# Spindle_Control.net
KiCad netlist of a schematic drawn in Altium Designer
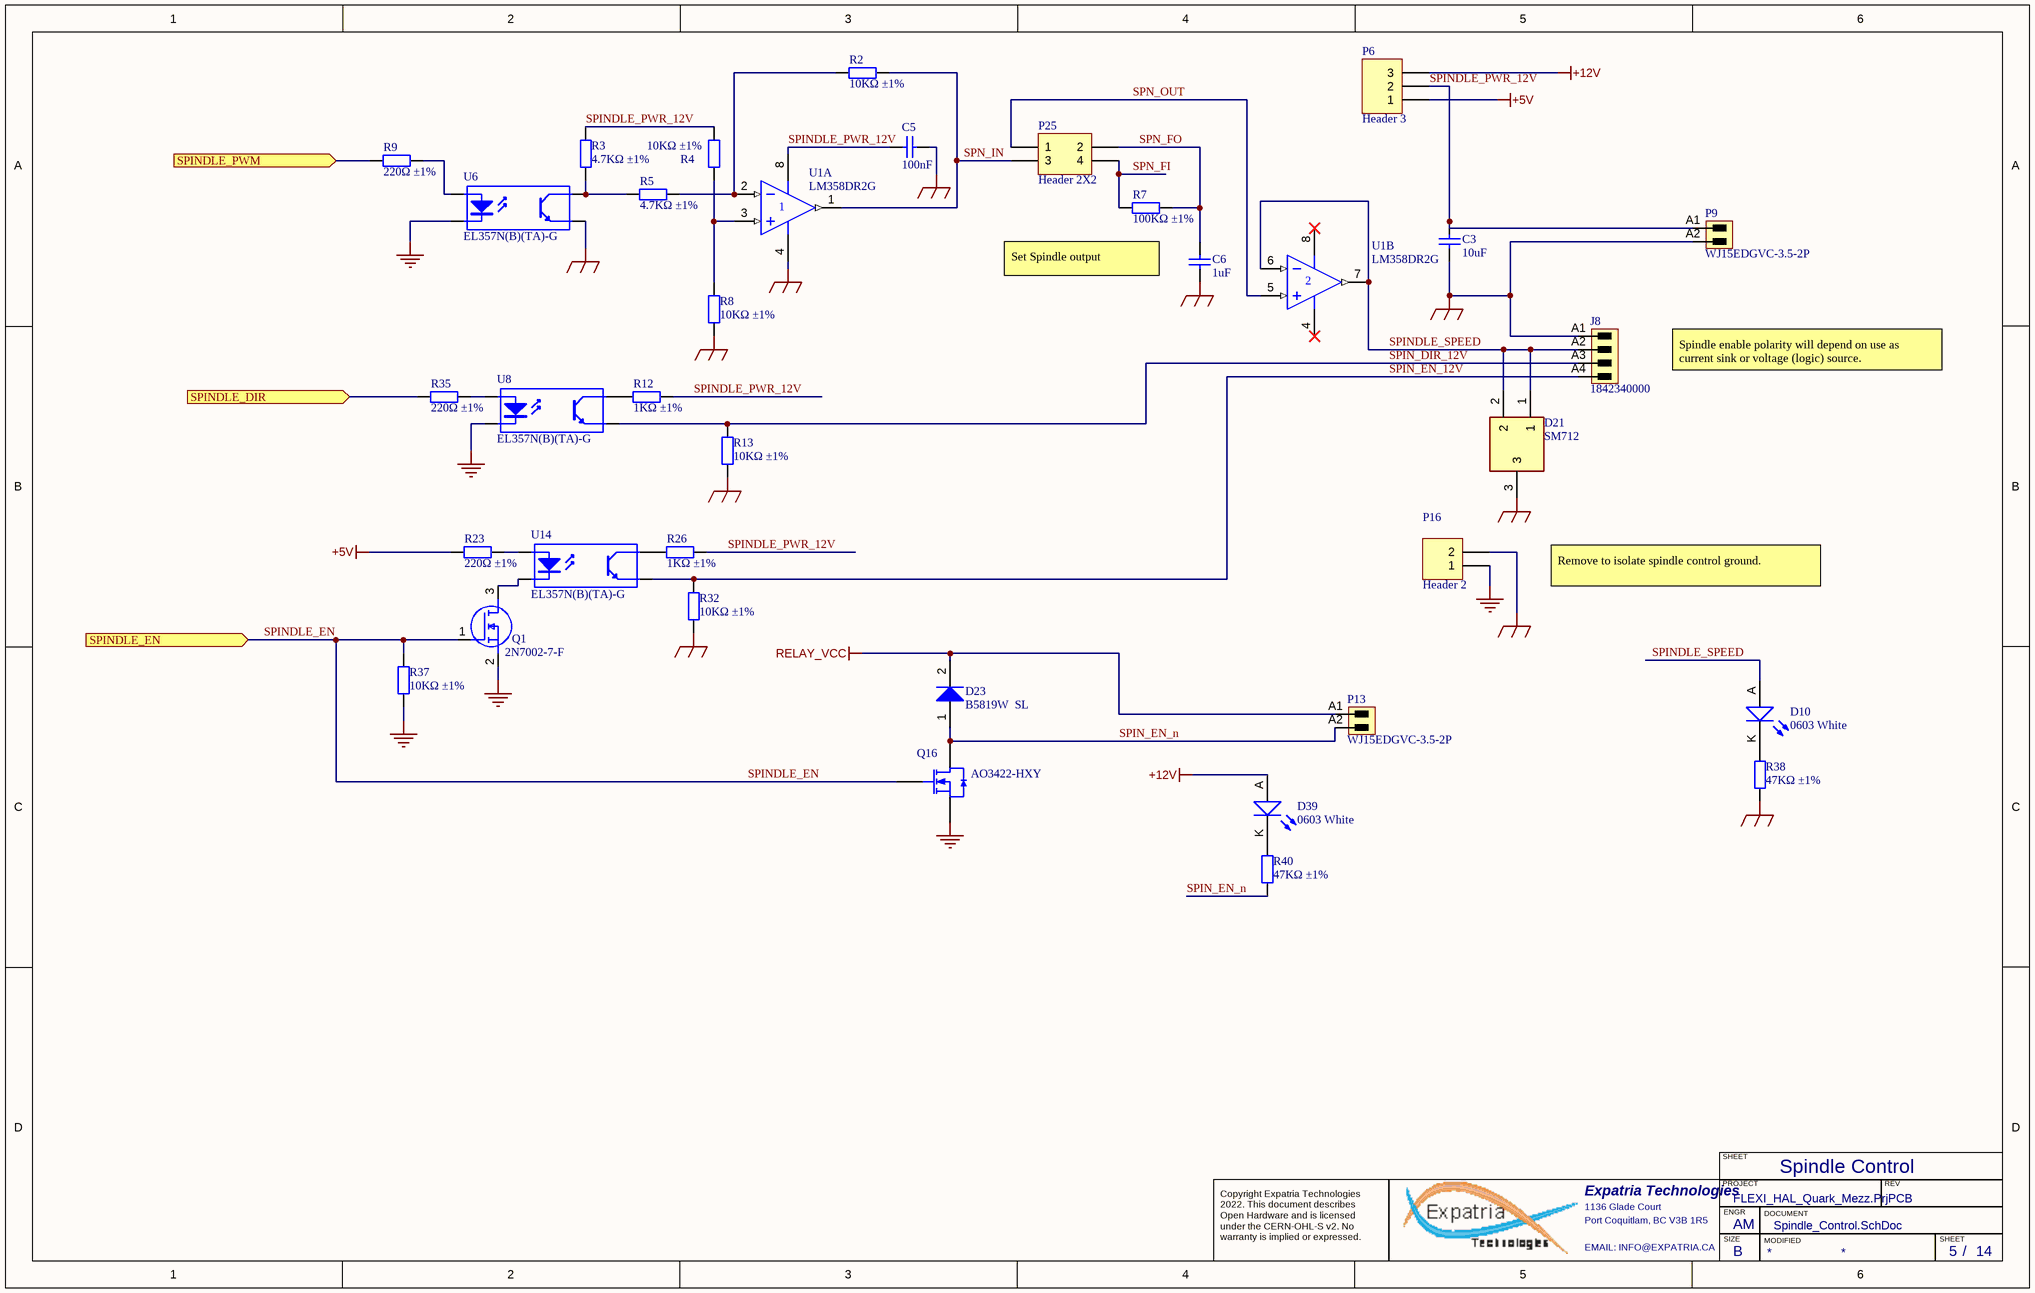
[diagram p0: Spindle_Control.SchDoc]

(export (version "E")
  (design (tool "Eeschema 10.0.6"))
  (components
    (comp (ref "C3")
      (value "10uF")
      (footprint "1206_C")
      (description "Chip capacitors")
      (fields
        (field (name "MANUFACTURER") "Samsung Electro-Mechanics")
        (field (name "PARTNUMBER") "CL31A106KBHNNNE")
      )
      (libsource (lib "Cap") (part "1206 10uF (106) 10% 50V"))
    )
    (comp (ref "C5")
      (value "100nF")
      (footprint "0603_C")
      (description "Chip capacitors")
      (fields (field (name "MANUFACTURER") "YAGEO") (field (name "PARTNUMBER") "CC0603KRX7R9BB104"))
      (libsource (lib "Cap") (part "0603 100nF (104) 10% 50V"))
    )
    (comp (ref "C6")
      (value "1uF")
      (footprint "0603_C")
      (description "Chip capacitors")
      (fields
        (field (name "MANUFACTURER") "Samsung Electro-Mechanics")
        (field (name "PARTNUMBER") "CL10A105KB8NNNC")
      )
      (libsource (lib "Cap") (part "0603 1uF (105) 10% 50V"))
    )
    (comp (ref "D10")
      (value "0603 White")
      (footprint "0603_LED_S1")
      (description "LED")
      (libsource (lib "LED") (part "0603 LED White"))
    )
    (comp (ref "D21")
      (value "SM712")
      (footprint "SamacSys:SOT95P230X117-3N")
      (description "Bidirectional 12V (Max), 7V (Max) 7.5V / 13.3V 10V / 20V 12A(8/20us) SOT-23-3 TVS RoHS")
      (libsource (lib "*") (part "CDSOT23-SM712"))
    )
    (comp (ref "D23")
      (value "B5819W  SL")
      (footprint "SOD-123")
      (description "Schottky Diode")
      (libsource (lib "Diode") (part "SOD-123 B5819W  SL"))
    )
    (comp (ref "D39")
      (value "0603 White")
      (footprint "0603_LED_S1")
      (description "LED")
      (libsource (lib "LED") (part "0603 LED White"))
    )
    (comp (ref "J8")
      (value "1842340000")
      (footprint "691321100004")
      (description "OMNIMATE Signal - series BL/SL 3.50")
      (libsource (lib "Universal_CNC_Breakout") (part "3.5mm Terminal Header 4p"))
    )
    (comp (ref "P6")
      (value "Header 3")
      (footprint "HDR1X3")
      (description "Header, 3-Pin")
      (fields (field (name "PUBLISHER") "Altium Limited"))
      (libsource (lib "Miscellaneous Connectors") (part "Header 3"))
    )
    (comp (ref "P9")
      (value "WJ15EDGVC-3.5-2P")
      (footprint "691321100002")
      (fields (field (name "MANUFACTURER") "Ningbo Kangnex Elec"))
      (libsource (lib "Universal_CNC_Breakout") (part "3.5mm Terminal Header 2p"))
    )
    (comp (ref "P13")
      (value "WJ15EDGVC-3.5-2P")
      (footprint "691321100002")
      (fields (field (name "MANUFACTURER") "Ningbo Kangnex Elec"))
      (libsource (lib "Universal_CNC_Breakout") (part "3.5mm Terminal Header 2p"))
    )
    (comp (ref "P16")
      (value "Header 2")
      (footprint "HDR1X2")
      (description "Header, 2-Pin")
      (fields (field (name "PUBLISHER") "Altium Limited"))
      (libsource (lib "Miscellaneous Connectors") (part "Header 2"))
    )
    (comp (ref "P25")
      (value "Header 2X2")
      (footprint "HDR2X2")
      (description "Header, 2-Pin, Dual row")
      (libsource (lib "Miscellaneous Connectors") (part "Header 2X2"))
    )
    (comp (ref "Q1")
      (value "2N7002-7-F")
      (footprint "SOT-23(SOT-23-3)")
      (description "60V 115mA 7.5Ω@5V,50mA 370mW N Channel SOT-23 MOSFETs ROHS")
      (fields (field (name "MANUFACTURER") "Diodes Inc.") (field (name "MOUSER PART NUMBER") "621-2N7002-F"))
      (libsource (lib "Sienci_Labs") (part "2N7002-7-F"))
    )
    (comp (ref "Q16")
      (value "AO3422-HXY")
      (footprint "SOT-23-3L")
      (description "60V 4.5A 8W 75mΩ@10V,5A 2.5V@250uA N Channel 695pF@15V SOT-23-3L MOSFETs ROHS")
      (libsource (lib "MOS") (part "AO3400A N道沟 X0YV1T SOT-23"))
    )
    (comp (ref "R2")
      (value "10KΩ ±1%")
      (footprint "0603_R")
      (description "Chip resistor")
      (fields (field (name "MANUFACTURER") "Uniroyal Elec") (field (name "PARTNUMBER") "0603WAF1002T5E"))
      (libsource (lib "") (part "0603 10K (1002) 1%_1"))
    )
    (comp (ref "R3")
      (value "4.7KΩ ±1%")
      (footprint "0603_R")
      (description "Chip resistor")
      (fields (field (name "MANUFACTURER") "Uniroyal Elec") (field (name "PARTNUMBER") "0603WAF4701T5E"))
      (libsource (lib "RES") (part "0603 4.7K (4701) 1%"))
    )
    (comp (ref "R4")
      (value "10KΩ ±1%")
      (footprint "0603_R")
      (description "Chip resistor")
      (fields (field (name "MANUFACTURER") "Uniroyal Elec") (field (name "PARTNUMBER") "0603WAF1002T5E"))
      (libsource (lib "RES") (part "0603 10K (1002) 1%"))
    )
    (comp (ref "R5")
      (value "4.7KΩ ±1%")
      (footprint "0603_R")
      (description "Chip resistor")
      (fields (field (name "MANUFACTURER") "Uniroyal Elec") (field (name "PARTNUMBER") "0603WAF4701T5E"))
      (libsource (lib "") (part "0603 4.7K (4701) 1%_1"))
    )
    (comp (ref "R7")
      (value "100KΩ ±1%")
      (footprint "0603_R")
      (description "Chip resistor")
      (fields (field (name "MANUFACTURER") "Uniroyal Elec") (field (name "PARTNUMBER") "0603WAF1003T5E"))
      (libsource (lib "RES") (part "0603 100K (1003) 1%"))
    )
    (comp (ref "R8")
      (value "10KΩ ±1%")
      (footprint "0603_R")
      (description "Chip resistor")
      (fields (field (name "MANUFACTURER") "Uniroyal Elec") (field (name "PARTNUMBER") "0603WAF1002T5E"))
      (libsource (lib "RES") (part "0603 10K (1002) 1%"))
    )
    (comp (ref "R9")
      (value "220Ω ±1%")
      (footprint "0402_R")
      (description "Chip resistor")
      (fields (field (name "MANUFACTURER") "Uniroyal Elec") (field (name "PARTNUMBER") "0402WGF2200TCE"))
      (libsource (lib "RES") (part "0402 220R (2200) 1%"))
    )
    (comp (ref "R12")
      (value "1KΩ ±1%")
      (footprint "0603_R")
      (description "Chip resistor")
      (fields (field (name "MANUFACTURER") "Uniroyal Elec") (field (name "PARTNUMBER") "0603WAF1001T5E"))
      (libsource (lib "RES") (part "0603 1K (1001) 1%"))
    )
    (comp (ref "R13")
      (value "10KΩ ±1%")
      (footprint "0603_R")
      (description "Chip resistor")
      (fields (field (name "MANUFACTURER") "Uniroyal Elec") (field (name "PARTNUMBER") "0603WAF1002T5E"))
      (libsource (lib "RES") (part "0603 10K (1002) 1%"))
    )
    (comp (ref "R23")
      (value "220Ω ±1%")
      (footprint "0603_R")
      (description "Chip resistor")
      (fields (field (name "MANUFACTURER") "Uniroyal Elec") (field (name "PARTNUMBER") "0603WAF2200T5E"))
      (libsource (lib "RES") (part "0603 220R (2200) 1%"))
    )
    (comp (ref "R26")
      (value "1KΩ ±1%")
      (footprint "0603_R")
      (description "Chip resistor")
      (fields (field (name "MANUFACTURER") "Uniroyal Elec") (field (name "PARTNUMBER") "0603WAF1001T5E"))
      (libsource (lib "RES") (part "0603 1K (1001) 1%"))
    )
    (comp (ref "R32")
      (value "10KΩ ±1%")
      (footprint "0603_R")
      (description "Chip resistor")
      (fields (field (name "MANUFACTURER") "Uniroyal Elec") (field (name "PARTNUMBER") "0603WAF1002T5E"))
      (libsource (lib "RES") (part "0603 10K (1002) 1%"))
    )
    (comp (ref "R35")
      (value "220Ω ±1%")
      (footprint "0603_R")
      (description "Chip resistor")
      (fields (field (name "MANUFACTURER") "Uniroyal Elec") (field (name "PARTNUMBER") "0603WAF2200T5E"))
      (libsource (lib "RES") (part "0603 220R (2200) 1%"))
    )
    (comp (ref "R37")
      (value "10KΩ ±1%")
      (footprint "0603_R")
      (description "Chip resistor")
      (fields (field (name "MANUFACTURER") "Uniroyal Elec") (field (name "PARTNUMBER") "0603WAF1002T5E"))
      (libsource (lib "RES") (part "0603 10K (1002) 1%"))
    )
    (comp (ref "R38")
      (value "47KΩ ±1%")
      (footprint "0603_R")
      (description "Chip resistor")
      (fields (field (name "MANUFACTURER") "Uniroyal Elec") (field (name "PARTNUMBER") "0603WAF4702T5E"))
      (libsource (lib "RES") (part "0603 47K (4702) 1%"))
    )
    (comp (ref "R40")
      (value "47KΩ ±1%")
      (footprint "0603_R")
      (description "Chip resistor")
      (fields (field (name "MANUFACTURER") "Uniroyal Elec") (field (name "PARTNUMBER") "0603WAF4702T5E"))
      (libsource (lib "RES") (part "0603 47K (4702) 1%"))
    )
    (comp (ref "U1")
      (value "LM358DR2G")
      (footprint "SOIC-8_150mil")
      (description "Dual Op Amp,  5 - 28 V,  8-PinSOIC")
      (libsource (lib "PrintNC_GRBLHAL_Breakout") (part "LM358DR2G_[C7950]"))
    )
    (comp (ref "U6")
      (value "EL357N(B)(TA)-G")
      (footprint "Miscellaneous Devices LC:SOP-4_P2.54")
      (description "OPTOISOLATOR 3.75KV TRANS 4-SOP")
      (libsource (lib "PrintNC_GRBLHAL_Breakout") (part "EL357N(B)(TA)-G_[C6649]"))
    )
    (comp (ref "U8")
      (value "EL357N(B)(TA)-G")
      (footprint "Miscellaneous Devices LC:SOP-4_P2.54")
      (description "OPTOISOLATOR 3.75KV TRANS 4-SOP")
      (libsource (lib "PrintNC_GRBLHAL_Breakout") (part "EL357N(B)(TA)-G_[C6649]"))
    )
    (comp (ref "U14")
      (value "EL357N(B)(TA)-G")
      (footprint "Miscellaneous Devices LC:SOP-4_P2.54")
      (description "OPTOISOLATOR 3.75KV TRANS 4-SOP")
      (libsource (lib "PrintNC_GRBLHAL_Breakout") (part "EL357N(B)(TA)-G_[C6649]"))
    )
  )
  (nets
    (net (code "1") (name "+5V") (class "Default")
      (node (ref "P6") (pin "1") (pinfunction "1_1") (pintype "passive"))
      (node (ref "R23") (pin "1") (pinfunction "1_1") (pintype "passive"))
    )
    (net (code "2") (name "+12V") (class "Default")
      (node (ref "D39") (pin "A") (pinfunction "A_A") (pintype "passive"))
      (node (ref "P6") (pin "3") (pinfunction "3_3") (pintype "passive"))
    )
    (net (code "3") (name "/SPINDLE_DIR") (class "Default")
      (node (ref "R35") (pin "1") (pinfunction "1_1") (pintype "passive"))
    )
    (net (code "4") (name "/SPINDLE_EN") (class "Default")
      (node (ref "Q1") (pin "1") (pinfunction "G_1") (pintype "passive"))
      (node (ref "Q16") (pin "1") (pinfunction "G_1") (pintype "passive"))
      (node (ref "R37") (pin "1") (pinfunction "1_1") (pintype "passive"))
    )
    (net (code "5") (name "/SPINDLE_PWM") (class "Default")
      (node (ref "R9") (pin "1") (pinfunction "1_1") (pintype "passive"))
    )
    (net (code "6") (name "/SPINDLE_PWR_12V") (class "Default")
      (node (ref "C3") (pin "2") (pinfunction "2_2") (pintype "passive"))
      (node (ref "C5") (pin "2") (pinfunction "2_2") (pintype "passive"))
      (node (ref "P6") (pin "2") (pinfunction "2_2") (pintype "passive"))
      (node (ref "P9") (pin "A1") (pinfunction "A1_A1") (pintype "passive"))
      (node (ref "R12") (pin "1") (pinfunction "1_1") (pintype "passive"))
      (node (ref "R26") (pin "1") (pinfunction "1_1") (pintype "passive"))
      (node (ref "R3") (pin "1") (pinfunction "1_1") (pintype "passive"))
      (node (ref "R4") (pin "1") (pinfunction "1_1") (pintype "passive"))
      (node (ref "U1") (pin "8") (pinfunction "V+_8") (pintype "power_in"))
    )
    (net (code "7") (name "/SPINDLE_SPEED") (class "Default")
      (node (ref "D10") (pin "A") (pinfunction "A_A") (pintype "passive"))
      (node (ref "D21") (pin "1") (pinfunction "1_1") (pintype "passive"))
      (node (ref "D21") (pin "2") (pinfunction "2_2") (pintype "passive"))
      (node (ref "J8") (pin "A2") (pinfunction "A2_A2") (pintype "passive"))
      (node (ref "U1") (pin "6") (pinfunction "IN-_6") (pintype "input"))
      (node (ref "U1") (pin "7") (pinfunction "OUT_7") (pintype "output"))
    )
    (net (code "8") (name "/SPIN_DIR_12V") (class "Default")
      (node (ref "J8") (pin "A3") (pinfunction "A3_A3") (pintype "passive"))
      (node (ref "R13") (pin "1") (pinfunction "1_1") (pintype "passive"))
      (node (ref "U8") (pin "3") (pinfunction "E_3") (pintype "passive"))
    )
    (net (code "9") (name "/SPIN_EN_12V") (class "Default")
      (node (ref "J8") (pin "A4") (pinfunction "A4_A4") (pintype "passive"))
      (node (ref "R32") (pin "1") (pinfunction "1_1") (pintype "passive"))
      (node (ref "U14") (pin "3") (pinfunction "E_3") (pintype "passive"))
    )
    (net (code "10") (name "/SPIN_EN_n") (class "Default")
      (node (ref "D23") (pin "1") (pinfunction "A_1") (pintype "passive"))
      (node (ref "P13") (pin "A2") (pinfunction "A2_A2") (pintype "passive"))
      (node (ref "Q16") (pin "3") (pinfunction "D_3") (pintype "passive"))
      (node (ref "R40") (pin "1") (pinfunction "1_1") (pintype "passive"))
    )
    (net (code "11") (name "/SPN_FI") (class "Default")
      (node (ref "P25") (pin "4") (pinfunction "4_4") (pintype "passive"))
      (node (ref "R7") (pin "2") (pinfunction "2_2") (pintype "passive"))
    )
    (net (code "12") (name "/SPN_FO") (class "Default")
      (node (ref "C6") (pin "2") (pinfunction "2_2") (pintype "passive"))
      (node (ref "P25") (pin "2") (pinfunction "2_2") (pintype "passive"))
      (node (ref "R7") (pin "1") (pinfunction "1_1") (pintype "passive"))
    )
    (net (code "13") (name "/SPN_IN") (class "Default")
      (node (ref "P25") (pin "3") (pinfunction "3_3") (pintype "passive"))
      (node (ref "R2") (pin "2") (pinfunction "2_2") (pintype "passive"))
      (node (ref "U1") (pin "1") (pinfunction "OUT_1") (pintype "output"))
    )
    (net (code "14") (name "/SPN_OUT") (class "Default")
      (node (ref "P25") (pin "1") (pinfunction "1_1") (pintype "passive"))
      (node (ref "U1") (pin "5") (pinfunction "IN+_5") (pintype "input"))
    )
    (net (code "15") (name "GND") (class "Default")
      (node (ref "P16") (pin "1") (pinfunction "1_1") (pintype "passive"))
      (node (ref "Q1") (pin "2") (pinfunction "S_2") (pintype "passive"))
      (node (ref "Q16") (pin "2") (pinfunction "S_2") (pintype "passive"))
      (node (ref "R37") (pin "2") (pinfunction "2_2") (pintype "passive"))
      (node (ref "U6") (pin "2") (pinfunction "K_2") (pintype "passive"))
      (node (ref "U8") (pin "2") (pinfunction "K_2") (pintype "passive"))
    )
    (net (code "16") (name "Net-(D10-PadK)") (class "Default")
      (node (ref "D10") (pin "K") (pinfunction "K_K") (pintype "passive"))
      (node (ref "R38") (pin "2") (pinfunction "2_2") (pintype "passive"))
    )
    (net (code "17") (name "Net-(D39-PadK)") (class "Default")
      (node (ref "D39") (pin "K") (pinfunction "K_K") (pintype "passive"))
      (node (ref "R40") (pin "2") (pinfunction "2_2") (pintype "passive"))
    )
    (net (code "18") (name "Net-(Q1-D)") (class "Default")
      (node (ref "Q1") (pin "3") (pinfunction "D_3") (pintype "passive"))
      (node (ref "U14") (pin "2") (pinfunction "K_2") (pintype "passive"))
    )
    (net (code "19") (name "Net-(U1A-IN+)") (class "Default")
      (node (ref "R4") (pin "2") (pinfunction "2_2") (pintype "passive"))
      (node (ref "R8") (pin "1") (pinfunction "1_1") (pintype "passive"))
      (node (ref "U1") (pin "3") (pinfunction "IN+_3") (pintype "input"))
    )
    (net (code "20") (name "Net-(U1A-IN-)") (class "Default")
      (node (ref "R2") (pin "1") (pinfunction "1_1") (pintype "passive"))
      (node (ref "R5") (pin "2") (pinfunction "2_2") (pintype "passive"))
      (node (ref "U1") (pin "2") (pinfunction "IN-_2") (pintype "input"))
    )
    (net (code "21") (name "Net-(U6-A)") (class "Default")
      (node (ref "R9") (pin "2") (pinfunction "2_2") (pintype "passive"))
      (node (ref "U6") (pin "1") (pinfunction "A_1") (pintype "passive"))
    )
    (net (code "22") (name "Net-(U6-C)") (class "Default")
      (node (ref "R3") (pin "2") (pinfunction "2_2") (pintype "passive"))
      (node (ref "R5") (pin "1") (pinfunction "1_1") (pintype "passive"))
      (node (ref "U6") (pin "4") (pinfunction "C_4") (pintype "passive"))
    )
    (net (code "23") (name "Net-(U8-A)") (class "Default")
      (node (ref "R35") (pin "2") (pinfunction "2_2") (pintype "passive"))
      (node (ref "U8") (pin "1") (pinfunction "A_1") (pintype "passive"))
    )
    (net (code "24") (name "Net-(U8-C)") (class "Default")
      (node (ref "R12") (pin "2") (pinfunction "2_2") (pintype "passive"))
      (node (ref "U8") (pin "4") (pinfunction "C_4") (pintype "passive"))
    )
    (net (code "25") (name "Net-(U14-A)") (class "Default")
      (node (ref "R23") (pin "2") (pinfunction "2_2") (pintype "passive"))
      (node (ref "U14") (pin "1") (pinfunction "A_1") (pintype "passive"))
    )
    (net (code "26") (name "Net-(U14-C)") (class "Default")
      (node (ref "R26") (pin "2") (pinfunction "2_2") (pintype "passive"))
      (node (ref "U14") (pin "4") (pinfunction "C_4") (pintype "passive"))
    )
    (net (code "27") (name "RELAY_VCC") (class "Default")
      (node (ref "D23") (pin "2") (pinfunction "K_2") (pintype "passive"))
      (node (ref "P13") (pin "A1") (pinfunction "A1_A1") (pintype "passive"))
    )
    (net (code "28") (name "SPIN_GND") (class "Default")
      (node (ref "C3") (pin "1") (pinfunction "1_1") (pintype "passive"))
      (node (ref "C5") (pin "1") (pinfunction "1_1") (pintype "passive"))
      (node (ref "C6") (pin "1") (pinfunction "1_1") (pintype "passive"))
      (node (ref "D21") (pin "3") (pinfunction "3_3") (pintype "passive"))
      (node (ref "J8") (pin "A1") (pinfunction "A1_A1") (pintype "passive"))
      (node (ref "P16") (pin "2") (pinfunction "2_2") (pintype "passive"))
      (node (ref "P9") (pin "A2") (pinfunction "A2_A2") (pintype "passive"))
      (node (ref "R13") (pin "2") (pinfunction "2_2") (pintype "passive"))
      (node (ref "R32") (pin "2") (pinfunction "2_2") (pintype "passive"))
      (node (ref "R38") (pin "1") (pinfunction "1_1") (pintype "passive"))
      (node (ref "R8") (pin "2") (pinfunction "2_2") (pintype "passive"))
      (node (ref "U1") (pin "4") (pinfunction "V-_4") (pintype "power_in"))
      (node (ref "U6") (pin "3") (pinfunction "E_3") (pintype "passive"))
    )
    (net (code "29") (name "unconnected-(U1B-V+-Pad8)") (class "Default")
      (node (ref "U1") (pin "8") (pinfunction "V+_8") (pintype "power_in+no_connect"))
    )
    (net (code "30") (name "unconnected-(U1B-V--Pad4)") (class "Default")
      (node (ref "U1") (pin "4") (pinfunction "V-_4") (pintype "power_in+no_connect"))
    )
  )
)
